# npm1300_qeaa_config2.net
KiCad netlist of a schematic drawn in Altium Designer
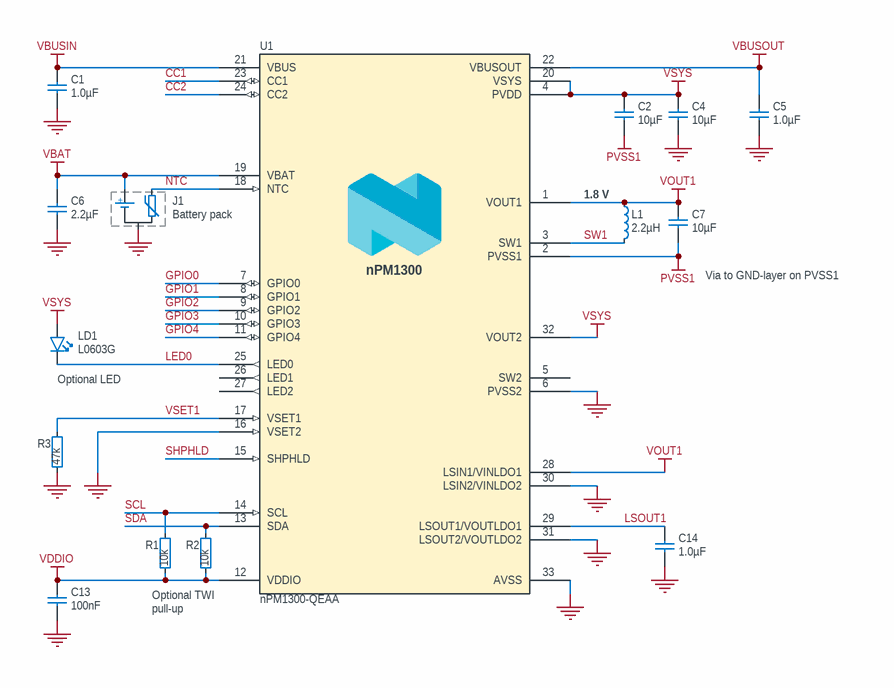
[diagram p0: npm1300_qeaa_config2.SchDoc]

(export (version "E")
  (design (tool "Eeschema 10.0.6"))
  (components
    (comp (ref "C1")
      (value "1.0µF")
      (footprint "CAPC1608X06L")
      (description "Capacitor, Ceramic, 1.0µF 10V X5R 0603,±10%")
      (fields
        (field (name "PART NUMBER") "C0603-1µ0-10V-X5R")
        (field (name "MANUFACTURER") "N.A.")
        (field (name "AUTHOR") "getr")
      )
      (libsource (lib "AltiumLib") (part "CAP"))
    )
    (comp (ref "C2")
      (value "10µF")
      (footprint "CAPC1608X06L")
      (description "Capacitor, Ceramic, X5R, ±20%, 10V")
      (fields
        (field (name "PART NUMBER") "C0603-10µ-10V-X5R")
        (field (name "MANUFACTURER") "N.A.")
        (field (name "AUTHOR") "rubr")
      )
      (libsource (lib "AltiumLib") (part "CAP"))
    )
    (comp (ref "C4")
      (value "10µF")
      (footprint "CAPC1608X06L")
      (description "Capacitor, Ceramic, X5R, ±20%, 10V")
      (fields
        (field (name "PART NUMBER") "C0603-10µ-10V-X5R")
        (field (name "MANUFACTURER") "N.A.")
        (field (name "AUTHOR") "rubr")
      )
      (libsource (lib "AltiumLib") (part "CAP"))
    )
    (comp (ref "C5")
      (value "1.0µF")
      (footprint "CAPC1608X06L")
      (description "Capacitor, Ceramic, 1.0µF 10V X5R 0603,±10%")
      (fields
        (field (name "PART NUMBER") "C0603-1µ0-10V-X5R")
        (field (name "MANUFACTURER") "N.A.")
        (field (name "AUTHOR") "getr")
      )
      (libsource (lib "AltiumLib") (part "CAP"))
    )
    (comp (ref "C6")
      (value "2.2µF")
      (footprint "CAPC1608X06L")
      (description "Capacitor, Ceramic, X5R, ±10%, 25V")
      (fields
        (field (name "PART NUMBER") "C0603-2µ2-25V-X5R-GRM188R61E225KA12D")
        (field (name "MANUFACTURER") "Murata")
        (field (name "AUTHOR") "rsk")
      )
      (libsource (lib "AltiumLib") (part "CAP"))
    )
    (comp (ref "C7")
      (value "10µF")
      (footprint "CAPC1608X06L")
      (description "Capacitor, Ceramic, X5R, ±20%, 10V")
      (fields
        (field (name "PART NUMBER") "C0603-10µ-10V-X5R")
        (field (name "MANUFACTURER") "N.A.")
        (field (name "AUTHOR") "rubr")
      )
      (libsource (lib "AltiumLib") (part "CAP"))
    )
    (comp (ref "C13")
      (value "100nF")
      (footprint "CAPC0603X03L_C")
      (description "Capacitor, Ceramic, X5R, ±10%, 25V")
      (fields
        (field (name "PART NUMBER") "C0201-100n-25V-X5R")
        (field (name "MANUFACTURER") "Murata")
        (field (name "AUTHOR") "rsk")
      )
      (libsource (lib "AltiumLib") (part "CAP"))
    )
    (comp (ref "C14")
      (value "1.0µF")
      (footprint "CAPC1608X06L")
      (description "Capacitor, Ceramic, 1.0µF 10V X5R 0603,±10%")
      (fields
        (field (name "PART NUMBER") "C0603-1µ0-10V-X5R")
        (field (name "MANUFACTURER") "N.A.")
        (field (name "AUTHOR") "getr")
      )
      (libsource (lib "AltiumLib") (part "CAP"))
    )
    (comp (ref "J1")
      (value "Battery pack")
      (footprint "TP_3x1mm_TH")
      (description "Battery pack with NTC")
      (fields
        (field (name "PART NUMBER") "Battery_w/NTC_TP")
        (field (name "MANUFACTURER") "N.A.")
        (field (name "AUTHOR") "rsk")
      )
      (libsource (lib "AltiumLib") (part "Battery_pack_NTC"))
    )
    (comp (ref "L1")
      (value "2.2µH")
      (footprint "INDC2016X10N")
      (description "Inductor, Irms=2.5A, Isat=2.9A, ±20%, DCR=73mΩ")
      (fields
        (field (name "PART NUMBER") "L0806-2µ2-2500mA-73mOhm-CIGT201610EH2R2MNE")
        (field (name "MANUFACTURER") "Samsung Electro-Mechanics America")
        (field (name "AUTHOR") "rsk")
      )
      (libsource (lib "AltiumLib") (part "IND"))
    )
    (comp (ref "LD1")
      (value "L0603G")
      (footprint "LED_0603_G")
      (description "LED 0603 GREEN")
      (fields
        (field (name "PART NUMBER") "150060GS55040")
        (field (name "MANUFACTURER") "Wurth Elektronik")
        (field (name "AUTHOR") "kjp")
      )
      (libsource (lib "AltiumLib") (part "D{colon}LED"))
    )
    (comp (ref "R1")
      (value "10k")
      (footprint "RESC0603X03L_C")
      (description "Resistor, ±1%, 0.05W")
      (fields
        (field (name "PART NUMBER") "R0201-10k")
        (field (name "MANUFACTURER") "N.A.")
        (field (name "AUTHOR") "rsk")
      )
      (libsource (lib "AltiumLib") (part "RES"))
    )
    (comp (ref "R2")
      (value "10k")
      (footprint "RESC0603X03L_C")
      (description "Resistor, ±1%, 0.05W")
      (fields
        (field (name "PART NUMBER") "R0201-10k")
        (field (name "MANUFACTURER") "N.A.")
        (field (name "AUTHOR") "rsk")
      )
      (libsource (lib "AltiumLib") (part "RES"))
    )
    (comp (ref "R3")
      (value "47k")
      (footprint "RESC0603X03L_C")
      (description "Resistor, ±1%, 0.05W")
      (fields
        (field (name "PART NUMBER") "R0201-47k")
        (field (name "MANUFACTURER") "N.A.")
        (field (name "AUTHOR") "rsk")
      )
      (libsource (lib "AltiumLib") (part "RES"))
    )
    (comp (ref "U1")
      (value "nPM1300-QEAA")
      (footprint "Nordic_QFN50P500X500X90-33N")
      (fields (field (name "MANUFACTURER") "Nordic Semiconductor") (field (name "AUTHOR") "eisk"))
      (libsource (lib "AltiumLib") (part "nPM1300_QEAA"))
    )
  )
  (nets
    (net (code "1") (name "/CC1") (class "Default")
      (node (ref "U1") (pin "23") (pinfunction "CC1_23") (pintype "bidirectional"))
    )
    (net (code "2") (name "/CC2") (class "Default")
      (node (ref "U1") (pin "24") (pinfunction "CC2_24") (pintype "bidirectional"))
    )
    (net (code "3") (name "/GPIO0") (class "Default")
      (node (ref "U1") (pin "7") (pinfunction "GPIO0_7") (pintype "bidirectional"))
    )
    (net (code "4") (name "/GPIO1") (class "Default")
      (node (ref "U1") (pin "8") (pinfunction "GPIO1_8") (pintype "bidirectional"))
    )
    (net (code "5") (name "/GPIO2") (class "Default")
      (node (ref "U1") (pin "9") (pinfunction "GPIO2_9") (pintype "bidirectional"))
    )
    (net (code "6") (name "/GPIO3") (class "Default")
      (node (ref "U1") (pin "10") (pinfunction "GPIO3_10") (pintype "bidirectional"))
    )
    (net (code "7") (name "/GPIO4") (class "Default")
      (node (ref "U1") (pin "11") (pinfunction "GPIO4_11") (pintype "bidirectional"))
    )
    (net (code "8") (name "/LED0") (class "Default")
      (node (ref "LD1") (pin "1") (pinfunction "C_1") (pintype "passive"))
      (node (ref "U1") (pin "25") (pinfunction "LED0_25") (pintype "output"))
    )
    (net (code "9") (name "/LSOUT1") (class "Default")
      (node (ref "C14") (pin "2") (pinfunction "2_2") (pintype "passive"))
      (node (ref "U1") (pin "29") (pinfunction "LSOUT1/VOUTLDO1_29") (pintype "power_in"))
    )
    (net (code "10") (name "/NTC") (class "Default")
      (node (ref "J1") (pin "2") (pinfunction "NTC_2") (pintype "passive"))
      (node (ref "U1") (pin "18") (pinfunction "NTC_18") (pintype "input"))
    )
    (net (code "11") (name "/SCL") (class "Default")
      (node (ref "R1") (pin "1") (pinfunction "1_1") (pintype "passive"))
      (node (ref "U1") (pin "14") (pinfunction "SCL_14") (pintype "input"))
    )
    (net (code "12") (name "/SDA") (class "Default")
      (node (ref "R2") (pin "1") (pinfunction "1_1") (pintype "passive"))
      (node (ref "U1") (pin "13") (pinfunction "SDA_13") (pintype "open_collector"))
    )
    (net (code "13") (name "/SHPHLD") (class "Default")
      (node (ref "U1") (pin "15") (pinfunction "SHPHLD_15") (pintype "input"))
    )
    (net (code "14") (name "/SW1") (class "Default")
      (node (ref "L1") (pin "2") (pinfunction "2_2") (pintype "passive"))
      (node (ref "U1") (pin "3") (pinfunction "SW1_3") (pintype "power_in"))
    )
    (net (code "15") (name "/VSET1") (class "Default")
      (node (ref "R3") (pin "1") (pinfunction "1_1") (pintype "passive"))
      (node (ref "U1") (pin "17") (pinfunction "VSET1_17") (pintype "input"))
    )
    (net (code "16") (name "GND") (class "Default")
      (node (ref "C1") (pin "1") (pinfunction "1_1") (pintype "passive"))
      (node (ref "C13") (pin "2") (pinfunction "2_2") (pintype "passive"))
      (node (ref "C14") (pin "1") (pinfunction "1_1") (pintype "passive"))
      (node (ref "C4") (pin "1") (pinfunction "1_1") (pintype "passive"))
      (node (ref "C5") (pin "1") (pinfunction "1_1") (pintype "passive"))
      (node (ref "C6") (pin "1") (pinfunction "1_1") (pintype "passive"))
      (node (ref "J1") (pin "1") (pinfunction "GND_1") (pintype "passive"))
      (node (ref "R3") (pin "2") (pinfunction "2_2") (pintype "passive"))
      (node (ref "U1") (pin "16") (pinfunction "VSET2_16") (pintype "input"))
      (node (ref "U1") (pin "30") (pinfunction "LSIN2/VINLDO2_30") (pintype "power_in"))
      (node (ref "U1") (pin "31") (pinfunction "LSOUT2/VOUTLDO2_31") (pintype "power_in"))
      (node (ref "U1") (pin "33") (pinfunction "AVSS_33") (pintype "power_in"))
      (node (ref "U1") (pin "6") (pinfunction "PVSS2_6") (pintype "power_in"))
    )
    (net (code "17") (name "PVSS1") (class "Default")
      (node (ref "C2") (pin "1") (pinfunction "1_1") (pintype "passive"))
      (node (ref "C7") (pin "1") (pinfunction "1_1") (pintype "passive"))
      (node (ref "U1") (pin "2") (pinfunction "PVSS1_2") (pintype "power_in"))
    )
    (net (code "18") (name "VBAT") (class "Default")
      (node (ref "C6") (pin "2") (pinfunction "2_2") (pintype "passive"))
      (node (ref "J1") (pin "3") (pinfunction "V+_3") (pintype "passive"))
      (node (ref "U1") (pin "19") (pinfunction "VBAT_19") (pintype "passive"))
    )
    (net (code "19") (name "VBUSIN") (class "Default")
      (node (ref "C1") (pin "2") (pinfunction "2_2") (pintype "passive"))
      (node (ref "U1") (pin "21") (pinfunction "VBUS_21") (pintype "power_in"))
    )
    (net (code "20") (name "VBUSOUT") (class "Default")
      (node (ref "C5") (pin "2") (pinfunction "2_2") (pintype "passive"))
      (node (ref "U1") (pin "22") (pinfunction "VBUSOUT_22") (pintype "power_in"))
    )
    (net (code "21") (name "VDDIO") (class "Default")
      (node (ref "C13") (pin "1") (pinfunction "1_1") (pintype "passive"))
      (node (ref "R1") (pin "2") (pinfunction "2_2") (pintype "passive"))
      (node (ref "R2") (pin "2") (pinfunction "2_2") (pintype "passive"))
      (node (ref "U1") (pin "12") (pinfunction "VDDIO_12") (pintype "power_in"))
    )
    (net (code "22") (name "VOUT1") (class "Default")
      (node (ref "C7") (pin "2") (pinfunction "2_2") (pintype "passive"))
      (node (ref "L1") (pin "1") (pinfunction "1_1") (pintype "passive"))
      (node (ref "U1") (pin "1") (pinfunction "VOUT1_1") (pintype "power_in"))
      (node (ref "U1") (pin "28") (pinfunction "LSIN1/VINLDO1_28") (pintype "power_in"))
    )
    (net (code "23") (name "VSYS") (class "Default")
      (node (ref "C2") (pin "2") (pinfunction "2_2") (pintype "passive"))
      (node (ref "C4") (pin "2") (pinfunction "2_2") (pintype "passive"))
      (node (ref "LD1") (pin "2") (pinfunction "A_2") (pintype "passive"))
      (node (ref "U1") (pin "20") (pinfunction "VSYS_20") (pintype "power_in"))
      (node (ref "U1") (pin "32") (pinfunction "VOUT2_32") (pintype "power_in"))
      (node (ref "U1") (pin "4") (pinfunction "PVDD_4") (pintype "power_in"))
    )
    (net (code "24") (name "unconnected-(U1-LED1-Pad26)") (class "Default")
      (node (ref "U1") (pin "26") (pinfunction "LED1_26") (pintype "output"))
    )
    (net (code "25") (name "unconnected-(U1-LED2-Pad27)") (class "Default")
      (node (ref "U1") (pin "27") (pinfunction "LED2_27") (pintype "output"))
    )
    (net (code "26") (name "unconnected-(U1-SW2-Pad5)") (class "Default")
      (node (ref "U1") (pin "5") (pinfunction "SW2_5") (pintype "power_in"))
    )
  )
)
